# 12V_Converter.net
KiCad netlist of a schematic drawn in Altium Designer
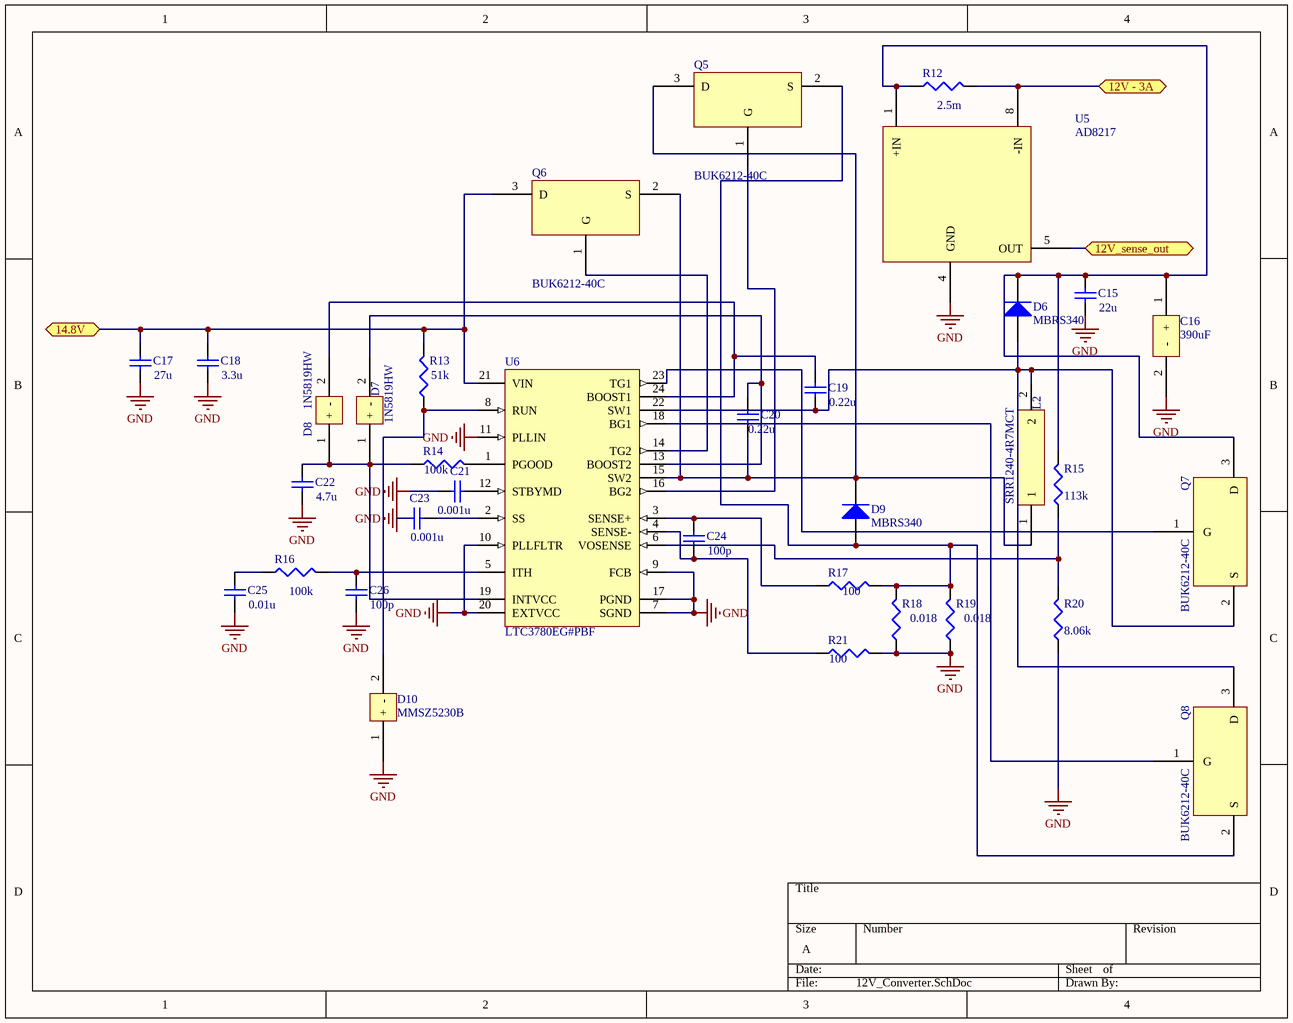
[diagram p0: 12V_Converter.SchDoc]

(export (version "E")
  (design (tool "Eeschema 10.0.6"))
  (components
    (comp (ref "C15")
      (value "22u")
      (footprint "C1206")
      (description "Capacitor (Semiconductor SIM Model)")
      (fields (field (name "Comment") "Cap Semi") (field (name "PUBLISHER") "Altium Limited"))
      (libsource (lib "Miscellaneous Devices") (part "Cap Semi"))
    )
    (comp (ref "C16")
      (value "390uF")
      (footprint "PCV1E391MCL2GS")
      (description "Aluminum Capacitor")
      (libsource (lib "Integrated_Library") (part "PCV1E391MCL2GS"))
    )
    (comp (ref "C17")
      (value "27u")
      (footprint "C1206")
      (description "Capacitor (Semiconductor SIM Model)")
      (fields (field (name "Comment") "Cap Semi") (field (name "PUBLISHER") "Altium Limited"))
      (libsource (lib "Miscellaneous Devices") (part "Cap Semi"))
    )
    (comp (ref "C18")
      (value "3.3u")
      (footprint "C1206")
      (description "Capacitor (Semiconductor SIM Model)")
      (fields (field (name "Comment") "Cap Semi") (field (name "PUBLISHER") "Altium Limited"))
      (libsource (lib "Miscellaneous Devices") (part "Cap Semi"))
    )
    (comp (ref "C19")
      (value "0.22u")
      (footprint "C1206")
      (description "Capacitor (Semiconductor SIM Model)")
      (fields (field (name "Comment") "Cap Semi") (field (name "PUBLISHER") "Altium Limited"))
      (libsource (lib "Miscellaneous Devices") (part "Cap Semi"))
    )
    (comp (ref "C20")
      (value "0.22u")
      (footprint "C1206")
      (description "Capacitor (Semiconductor SIM Model)")
      (fields (field (name "Comment") "Cap Semi") (field (name "PUBLISHER") "Altium Limited"))
      (libsource (lib "Miscellaneous Devices") (part "Cap Semi"))
    )
    (comp (ref "C21")
      (value "0.001u")
      (footprint "C1206")
      (description "Capacitor (Semiconductor SIM Model)")
      (fields (field (name "Comment") "Cap Semi") (field (name "PUBLISHER") "Altium Limited"))
      (libsource (lib "Miscellaneous Devices") (part "Cap Semi"))
    )
    (comp (ref "C22")
      (value "4.7u")
      (footprint "C1206")
      (description "Capacitor (Semiconductor SIM Model)")
      (fields (field (name "Comment") "Cap Semi") (field (name "PUBLISHER") "Altium Limited"))
      (libsource (lib "Miscellaneous Devices") (part "Cap Semi"))
    )
    (comp (ref "C23")
      (value "0.001u")
      (footprint "C1206")
      (description "Capacitor (Semiconductor SIM Model)")
      (fields (field (name "Comment") "Cap Semi") (field (name "PUBLISHER") "Altium Limited"))
      (libsource (lib "Miscellaneous Devices") (part "Cap Semi"))
    )
    (comp (ref "C24")
      (value "100p")
      (footprint "C1206")
      (description "Capacitor (Semiconductor SIM Model)")
      (fields (field (name "Comment") "Cap Semi") (field (name "PUBLISHER") "Altium Limited"))
      (libsource (lib "Miscellaneous Devices") (part "Cap Semi"))
    )
    (comp (ref "C25")
      (value "0.01u")
      (footprint "C1206")
      (description "Capacitor (Semiconductor SIM Model)")
      (fields (field (name "Comment") "Cap Semi") (field (name "PUBLISHER") "Altium Limited"))
      (libsource (lib "Miscellaneous Devices") (part "Cap Semi"))
    )
    (comp (ref "C26")
      (value "100p")
      (footprint "C1206")
      (description "Capacitor (Semiconductor SIM Model)")
      (fields (field (name "Comment") "Cap Semi") (field (name "PUBLISHER") "Altium Limited"))
      (libsource (lib "Miscellaneous Devices") (part "Cap Semi"))
    )
    (comp (ref "D6")
      (value "MBRS340")
      (footprint "SMC")
      (description "Default Diode")
      (fields (field (name "PUBLISHER") "Altium Limited"))
      (libsource (lib "Miscellaneous Devices") (part "Diode"))
    )
    (comp (ref "D7")
      (value "1N5819HW")
      (footprint "1N5819HW")
      (description "1A Schottky Barrier Rectifier")
      (libsource (lib "Integrated_Library") (part "1N5819HW"))
    )
    (comp (ref "D8")
      (value "1N5819HW")
      (footprint "1N5819HW")
      (description "1A Schottky Barrier Rectifier")
      (libsource (lib "Integrated_Library") (part "1N5819HW"))
    )
    (comp (ref "D9")
      (value "MBRS340")
      (footprint "SMC")
      (description "Default Diode")
      (fields (field (name "PUBLISHER") "Altium Limited"))
      (libsource (lib "Miscellaneous Devices") (part "Diode"))
    )
    (comp (ref "D10")
      (value "MMSZ5230B")
      (footprint "MMSZ5230B")
      (description "Zener Diode")
      (libsource (lib "Integrated_Library") (part "MMSZ5230B"))
    )
    (comp (ref "L2")
      (value "SRR1240-4R7MCT")
      (footprint "SRR1240-4R7M")
      (description "Inductor")
      (libsource (lib "Integrated_Library") (part "SRR1240-4R7MCT"))
    )
    (comp (ref "Q5")
      (value "BUK6212-40C")
      (footprint "BUK6212-40C")
      (description "N-Channel TrenchMOS Intermediate Level FET")
      (libsource (lib "Integrated_Library") (part "BUK6212-40C"))
    )
    (comp (ref "Q6")
      (value "BUK6212-40C")
      (footprint "BUK6212-40C")
      (description "N-Channel TrenchMOS Intermediate Level FET")
      (libsource (lib "Integrated_Library") (part "BUK6212-40C"))
    )
    (comp (ref "Q7")
      (value "BUK6212-40C")
      (footprint "BUK6212-40C")
      (description "N-Channel TrenchMOS Intermediate Level FET")
      (libsource (lib "") (part "BUK6212-40C_1"))
    )
    (comp (ref "Q8")
      (value "BUK6212-40C")
      (footprint "BUK6212-40C")
      (description "N-Channel TrenchMOS Intermediate Level FET")
      (libsource (lib "") (part "BUK6212-40C_1"))
    )
    (comp (ref "R12")
      (value "2.5m")
      (footprint "J1-0603")
      (description "Resistor")
      (fields (field (name "Comment") "Res3") (field (name "PUBLISHER") "Altium Limited"))
      (libsource (lib "Miscellaneous Devices") (part "Res3"))
    )
    (comp (ref "R13")
      (value "51k")
      (footprint "J1-0603")
      (description "Resistor")
      (fields (field (name "Comment") "Res3") (field (name "PUBLISHER") "Altium Limited"))
      (libsource (lib "Miscellaneous Devices") (part "Res3"))
    )
    (comp (ref "R14")
      (value "100k")
      (footprint "J1-0603")
      (description "Resistor")
      (fields (field (name "Comment") "Res3") (field (name "PUBLISHER") "Altium Limited"))
      (libsource (lib "Miscellaneous Devices") (part "Res3"))
    )
    (comp (ref "R15")
      (value "113k")
      (footprint "J1-0603")
      (description "Resistor")
      (fields (field (name "Comment") "Res3") (field (name "PUBLISHER") "Altium Limited"))
      (libsource (lib "Miscellaneous Devices") (part "Res3"))
    )
    (comp (ref "R16")
      (value "100k")
      (footprint "J1-0603")
      (description "Resistor")
      (fields (field (name "Comment") "Res3") (field (name "PUBLISHER") "Altium Limited"))
      (libsource (lib "Miscellaneous Devices") (part "Res3"))
    )
    (comp (ref "R17")
      (value "100")
      (footprint "J1-0603")
      (description "Resistor")
      (fields (field (name "Comment") "Res3") (field (name "PUBLISHER") "Altium Limited"))
      (libsource (lib "Miscellaneous Devices") (part "Res3"))
    )
    (comp (ref "R18")
      (value "0.018")
      (footprint "J1-0603")
      (description "Resistor")
      (fields (field (name "Comment") "Res3") (field (name "PUBLISHER") "Altium Limited"))
      (libsource (lib "Miscellaneous Devices") (part "Res3"))
    )
    (comp (ref "R19")
      (value "0.018")
      (footprint "J1-0603")
      (description "Resistor")
      (fields (field (name "Comment") "Res3") (field (name "PUBLISHER") "Altium Limited"))
      (libsource (lib "Miscellaneous Devices") (part "Res3"))
    )
    (comp (ref "R20")
      (value "8.06k")
      (footprint "J1-0603")
      (description "Resistor")
      (fields (field (name "Comment") "Res3") (field (name "PUBLISHER") "Altium Limited"))
      (libsource (lib "Miscellaneous Devices") (part "Res3"))
    )
    (comp (ref "R21")
      (value "100")
      (footprint "J1-0603")
      (description "Resistor")
      (fields (field (name "Comment") "Res3") (field (name "PUBLISHER") "Altium Limited"))
      (libsource (lib "Miscellaneous Devices") (part "Res3"))
    )
    (comp (ref "U5")
      (value "AD8217")
      (footprint "AD8217")
      (description "Current Shunt Moniter")
      (libsource (lib "Integrated_Library") (part "AD8217"))
    )
    (comp (ref "U6")
      (value "LTC3780EG#PBF")
      (footprint "LTC3780 24-Leaqd Plastic SSOP")
      (fields (field (name "MANUFACTURER") "Linear Technology"))
      (libsource (lib "Integrated_Library") (part "LTC3780EG#PBF"))
    )
  )
  (nets
    (net (code "1") (name "/12V - 3A") (class "Default")
      (node (ref "R12") (pin "2") (pinfunction "2_2") (pintype "passive"))
      (node (ref "U5") (pin "8") (pinfunction "-IN_8") (pintype "passive"))
    )
    (net (code "2") (name "/12V_sense_out") (class "Default")
      (node (ref "U5") (pin "5") (pinfunction "OUT_5") (pintype "passive"))
    )
    (net (code "3") (name "/14.8V") (class "Default")
      (node (ref "C17") (pin "2") (pinfunction "2_2") (pintype "passive"))
      (node (ref "C18") (pin "2") (pinfunction "2_2") (pintype "passive"))
      (node (ref "Q6") (pin "3") (pinfunction "D_3") (pintype "passive"))
      (node (ref "R13") (pin "2") (pinfunction "2_2") (pintype "passive"))
      (node (ref "U6") (pin "21") (pinfunction "VIN_21") (pintype "power_in"))
    )
    (net (code "4") (name "GND") (class "Default")
      (node (ref "C15") (pin "1") (pinfunction "1_1") (pintype "passive"))
      (node (ref "C16") (pin "2") (pinfunction "-_2") (pintype "passive"))
      (node (ref "C17") (pin "1") (pinfunction "1_1") (pintype "passive"))
      (node (ref "C18") (pin "1") (pinfunction "1_1") (pintype "passive"))
      (node (ref "C21") (pin "1") (pinfunction "1_1") (pintype "passive"))
      (node (ref "C22") (pin "1") (pinfunction "1_1") (pintype "passive"))
      (node (ref "C23") (pin "1") (pinfunction "1_1") (pintype "passive"))
      (node (ref "C25") (pin "1") (pinfunction "1_1") (pintype "passive"))
      (node (ref "C26") (pin "1") (pinfunction "1_1") (pintype "passive"))
      (node (ref "D10") (pin "1") (pinfunction "+_1") (pintype "passive"))
      (node (ref "R18") (pin "1") (pinfunction "1_1") (pintype "passive"))
      (node (ref "R19") (pin "1") (pinfunction "1_1") (pintype "passive"))
      (node (ref "R20") (pin "1") (pinfunction "1_1") (pintype "passive"))
      (node (ref "R21") (pin "2") (pinfunction "2_2") (pintype "passive"))
      (node (ref "U5") (pin "4") (pinfunction "GND_4") (pintype "passive"))
      (node (ref "U6") (pin "10") (pinfunction "PLLFLTR_10") (pintype "input"))
      (node (ref "U6") (pin "11") (pinfunction "PLLIN_11") (pintype "input"))
      (node (ref "U6") (pin "17") (pinfunction "PGND_17") (pintype "power_in"))
      (node (ref "U6") (pin "20") (pinfunction "EXTVCC_20") (pintype "power_in"))
      (node (ref "U6") (pin "7") (pinfunction "SGND_7") (pintype "power_in"))
      (node (ref "U6") (pin "9") (pinfunction "FCB_9") (pintype "input"))
    )
    (net (code "5") (name "Net-(C16-+)") (class "Default")
      (node (ref "C15") (pin "2") (pinfunction "2_2") (pintype "passive"))
      (node (ref "C16") (pin "1") (pinfunction "+_1") (pintype "passive"))
      (node (ref "D6") (pin "2") (pinfunction "K_2") (pintype "passive"))
      (node (ref "Q7") (pin "3") (pinfunction "D_3") (pintype "passive"))
      (node (ref "R12") (pin "1") (pinfunction "1_1") (pintype "passive"))
      (node (ref "R15") (pin "2") (pinfunction "2_2") (pintype "passive"))
      (node (ref "U5") (pin "1") (pinfunction "+IN_1") (pintype "passive"))
    )
    (net (code "6") (name "Net-(C25-Pad2)") (class "Default")
      (node (ref "C25") (pin "2") (pinfunction "2_2") (pintype "passive"))
      (node (ref "R16") (pin "1") (pinfunction "1_1") (pintype "passive"))
    )
    (net (code "7") (name "Net-(D6-A)") (class "Default")
      (node (ref "C19") (pin "1") (pinfunction "1_1") (pintype "passive"))
      (node (ref "D6") (pin "1") (pinfunction "A_1") (pintype "passive"))
      (node (ref "L2") (pin "2") (pinfunction "2_2") (pintype "passive"))
      (node (ref "Q7") (pin "2") (pinfunction "S_2") (pintype "passive"))
      (node (ref "Q8") (pin "3") (pinfunction "D_3") (pintype "passive"))
      (node (ref "U6") (pin "22") (pinfunction "SW1_22") (pintype "passive"))
    )
    (net (code "8") (name "Net-(D7-+)") (class "Default")
      (node (ref "C22") (pin "2") (pinfunction "2_2") (pintype "passive"))
      (node (ref "D7") (pin "1") (pinfunction "+_1") (pintype "passive"))
      (node (ref "D8") (pin "1") (pinfunction "+_1") (pintype "passive"))
      (node (ref "R14") (pin "1") (pinfunction "1_1") (pintype "passive"))
      (node (ref "U6") (pin "19") (pinfunction "INTVCC_19") (pintype "power_in"))
    )
    (net (code "9") (name "Net-(D7--)") (class "Default")
      (node (ref "C20") (pin "2") (pinfunction "2_2") (pintype "passive"))
      (node (ref "D7") (pin "2") (pinfunction "-_2") (pintype "passive"))
      (node (ref "U6") (pin "13") (pinfunction "BOOST2_13") (pintype "passive"))
    )
    (net (code "10") (name "Net-(D8--)") (class "Default")
      (node (ref "C19") (pin "2") (pinfunction "2_2") (pintype "passive"))
      (node (ref "D8") (pin "2") (pinfunction "-_2") (pintype "passive"))
      (node (ref "U6") (pin "24") (pinfunction "BOOST1_24") (pintype "passive"))
    )
    (net (code "11") (name "Net-(D9-A)") (class "Default")
      (node (ref "D9") (pin "1") (pinfunction "A_1") (pintype "passive"))
      (node (ref "Q5") (pin "2") (pinfunction "S_2") (pintype "passive"))
      (node (ref "Q8") (pin "2") (pinfunction "S_2") (pintype "passive"))
      (node (ref "R17") (pin "2") (pinfunction "2_2") (pintype "passive"))
      (node (ref "R18") (pin "2") (pinfunction "2_2") (pintype "passive"))
      (node (ref "R19") (pin "2") (pinfunction "2_2") (pintype "passive"))
    )
    (net (code "12") (name "Net-(D9-K)") (class "Default")
      (node (ref "C20") (pin "1") (pinfunction "1_1") (pintype "passive"))
      (node (ref "D9") (pin "2") (pinfunction "K_2") (pintype "passive"))
      (node (ref "L2") (pin "1") (pinfunction "1_1") (pintype "passive"))
      (node (ref "Q5") (pin "3") (pinfunction "D_3") (pintype "passive"))
      (node (ref "Q6") (pin "2") (pinfunction "S_2") (pintype "passive"))
      (node (ref "U6") (pin "15") (pinfunction "SW2_15") (pintype "passive"))
    )
    (net (code "13") (name "Net-(D10--)") (class "Default")
      (node (ref "D10") (pin "2") (pinfunction "-_2") (pintype "passive"))
      (node (ref "R13") (pin "1") (pinfunction "1_1") (pintype "passive"))
      (node (ref "U6") (pin "8") (pinfunction "RUN_8") (pintype "input"))
    )
    (net (code "14") (name "Net-(Q5-G)") (class "Default")
      (node (ref "Q5") (pin "1") (pinfunction "G_1") (pintype "passive"))
      (node (ref "U6") (pin "16") (pinfunction "BG2_16") (pintype "output"))
    )
    (net (code "15") (name "Net-(Q6-G)") (class "Default")
      (node (ref "Q6") (pin "1") (pinfunction "G_1") (pintype "passive"))
      (node (ref "U6") (pin "14") (pinfunction "TG2_14") (pintype "output"))
    )
    (net (code "16") (name "Net-(Q7-G)") (class "Default")
      (node (ref "Q7") (pin "1") (pinfunction "G_1") (pintype "passive"))
      (node (ref "U6") (pin "23") (pinfunction "TG1_23") (pintype "output"))
    )
    (net (code "17") (name "Net-(Q8-G)") (class "Default")
      (node (ref "Q8") (pin "1") (pinfunction "G_1") (pintype "passive"))
      (node (ref "U6") (pin "18") (pinfunction "BG1_18") (pintype "output"))
    )
    (net (code "18") (name "Net-(U6-ITH)") (class "Default")
      (node (ref "C26") (pin "2") (pinfunction "2_2") (pintype "passive"))
      (node (ref "R16") (pin "2") (pinfunction "2_2") (pintype "passive"))
      (node (ref "U6") (pin "5") (pinfunction "ITH_5") (pintype "passive"))
    )
    (net (code "19") (name "Net-(U6-PGOOD)") (class "Default")
      (node (ref "R14") (pin "2") (pinfunction "2_2") (pintype "passive"))
      (node (ref "U6") (pin "1") (pinfunction "PGOOD_1") (pintype "open_collector"))
    )
    (net (code "20") (name "Net-(U6-SENSE+)") (class "Default")
      (node (ref "C24") (pin "2") (pinfunction "2_2") (pintype "passive"))
      (node (ref "R17") (pin "1") (pinfunction "1_1") (pintype "passive"))
      (node (ref "U6") (pin "3") (pinfunction "SENSE+_3") (pintype "input"))
    )
    (net (code "21") (name "Net-(U6-SENSE-)") (class "Default")
      (node (ref "C24") (pin "1") (pinfunction "1_1") (pintype "passive"))
      (node (ref "R21") (pin "1") (pinfunction "1_1") (pintype "passive"))
      (node (ref "U6") (pin "4") (pinfunction "SENSE-_4") (pintype "input"))
    )
    (net (code "22") (name "Net-(U6-SS)") (class "Default")
      (node (ref "C23") (pin "2") (pinfunction "2_2") (pintype "passive"))
      (node (ref "U6") (pin "2") (pinfunction "SS_2") (pintype "input"))
    )
    (net (code "23") (name "Net-(U6-STBYMD)") (class "Default")
      (node (ref "C21") (pin "2") (pinfunction "2_2") (pintype "passive"))
      (node (ref "U6") (pin "12") (pinfunction "STBYMD_12") (pintype "input"))
    )
    (net (code "24") (name "Net-(U6-VOSENSE)") (class "Default")
      (node (ref "R15") (pin "1") (pinfunction "1_1") (pintype "passive"))
      (node (ref "R20") (pin "2") (pinfunction "2_2") (pintype "passive"))
      (node (ref "U6") (pin "6") (pinfunction "VOSENSE_6") (pintype "input"))
    )
  )
)
